# 8266_Download.net
KiCad netlist of a schematic drawn in Altium Designer
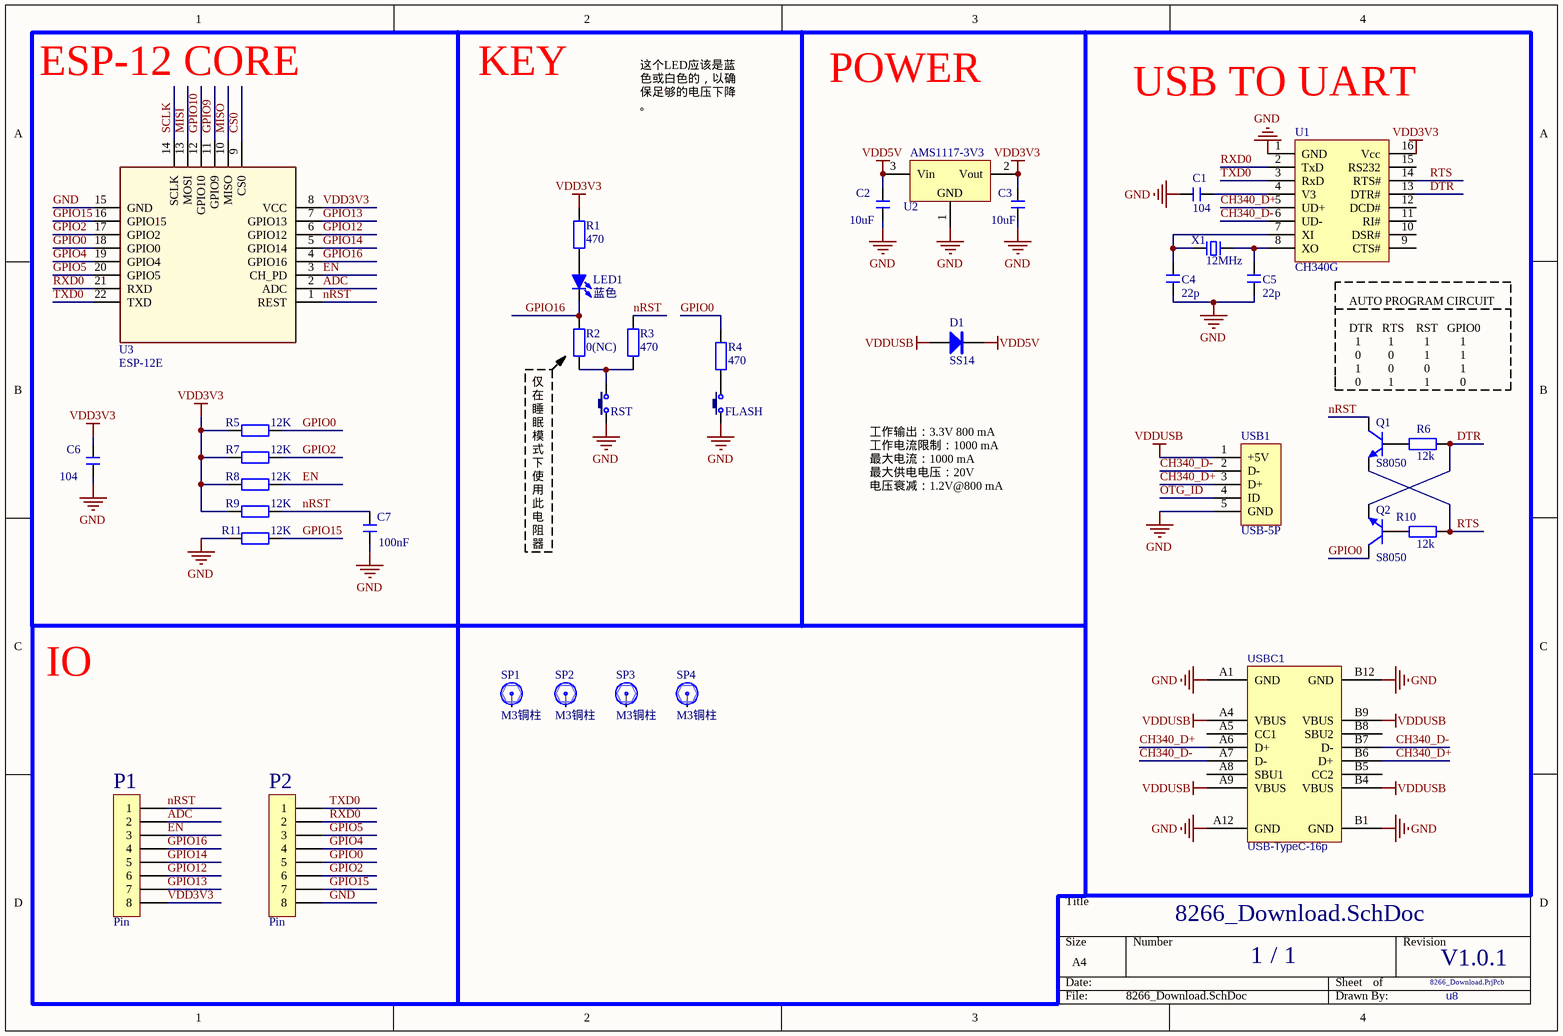
[diagram p0: 8266_Download.SchDoc]

(export (version "E")
  (design (tool "Eeschema 10.0.6"))
  (components
    (comp (ref "C1")
      (value "104")
      (footprint "C 0603_M")
      (description "无极性贴片电容")
      (fields (field (name "版权归属") "源创客"))
      (libsource (lib "U8Library") (part "C"))
    )
    (comp (ref "C2")
      (value "10uF")
      (footprint "C 0603_M")
      (description "无极性贴片电容")
      (fields (field (name "版权归属") "源创客"))
      (libsource (lib "U8Library") (part "C"))
    )
    (comp (ref "C3")
      (value "10uF")
      (footprint "C 0603_M")
      (description "无极性贴片电容")
      (fields (field (name "版权归属") "源创客"))
      (libsource (lib "U8Library") (part "C"))
    )
    (comp (ref "C4")
      (value "22p")
      (footprint "C 0603_M")
      (description "无极性贴片电容")
      (fields (field (name "版权归属") "源创客"))
      (libsource (lib "U8Library") (part "C"))
    )
    (comp (ref "C5")
      (value "22p")
      (footprint "C 0603_M")
      (description "无极性贴片电容")
      (fields (field (name "版权归属") "源创客"))
      (libsource (lib "U8Library") (part "C"))
    )
    (comp (ref "C6")
      (value "104")
      (footprint "C 0603_M")
      (description "无极性贴片电容")
      (fields (field (name "版权归属") "源创客"))
      (libsource (lib "U8Library") (part "C"))
    )
    (comp (ref "C7")
      (value "100nF")
      (footprint "C 0603_M")
      (description "无极性贴片电容")
      (fields (field (name "版权归属") "源创客"))
      (libsource (lib "U8Library") (part "C"))
    )
    (comp (ref "D1")
      (value "SS14")
      (footprint "SMA")
      (description "肖特基二极管")
      (fields (field (name "版权归属") "源创客"))
      (libsource (lib "U8Library") (part "SS14"))
    )
    (comp (ref "FLASH")
      (value "3x6x5")
      (footprint "TSW SMD-3*6*2.5")
      (description "3x6轻触开关")
      (fields (field (name "版权归属") "源创客"))
      (libsource (lib "U8Library") (part "TSW 3x6"))
    )
    (comp (ref "LED1")
      (value "蓝色")
      (footprint "LED 0603B")
      (description "贴片LED")
      (fields (field (name "版权归属") "源创客"))
      (libsource (lib "U8Library") (part "LED-SMD"))
    )
    (comp (ref "P1")
      (value "Pin")
      (footprint "Header_D_8_8x1_2.54")
      (libsource (lib "MZ_接插件库") (part "Header_D_8_8x1_2.54"))
    )
    (comp (ref "P2")
      (value "Pin")
      (footprint "Header_D_8_8x1_2.54")
      (libsource (lib "MZ_接插件库") (part "Header_D_8_8x1_2.54"))
    )
    (comp (ref "Q1")
      (value "S8050")
      (footprint "SOT23-3N")
      (description "高频放大-NPN型")
      (fields (field (name "版权归属") "源创客"))
      (libsource (lib "U8Library") (part "8050-SMD"))
    )
    (comp (ref "Q2")
      (value "S8050")
      (footprint "SOT23-3N")
      (description "高频放大-NPN型")
      (fields (field (name "版权归属") "源创客"))
      (libsource (lib "U8Library") (part "8050-SMD"))
    )
    (comp (ref "R1")
      (value "470")
      (footprint "R 0603_M")
      (description "贴片电阻")
      (fields (field (name "版权归属") "源创客"))
      (libsource (lib "U8Library") (part "R"))
    )
    (comp (ref "R2")
      (value "0(NC)")
      (footprint "R 0603_M")
      (description "贴片电阻")
      (fields (field (name "版权归属") "源创客"))
      (libsource (lib "U8Library") (part "R"))
    )
    (comp (ref "R3")
      (value "470")
      (footprint "R 0603_M")
      (description "贴片电阻")
      (fields (field (name "版权归属") "源创客"))
      (libsource (lib "U8Library") (part "R"))
    )
    (comp (ref "R4")
      (value "470")
      (footprint "R 0603_M")
      (description "贴片电阻")
      (fields (field (name "版权归属") "源创客"))
      (libsource (lib "U8Library") (part "R"))
    )
    (comp (ref "R5")
      (value "12K")
      (footprint "R 0603_M")
      (description "贴片电阻")
      (fields (field (name "版权归属") "源创客"))
      (libsource (lib "U8Library") (part "R"))
    )
    (comp (ref "R6")
      (value "12k")
      (footprint "R 0603_M")
      (description "贴片电阻")
      (fields (field (name "版权归属") "源创客"))
      (libsource (lib "U8Library") (part "R"))
    )
    (comp (ref "R7")
      (value "12K")
      (footprint "R 0603_M")
      (description "贴片电阻")
      (fields (field (name "版权归属") "源创客"))
      (libsource (lib "U8Library") (part "R"))
    )
    (comp (ref "R8")
      (value "12K")
      (footprint "R 0603_M")
      (description "贴片电阻")
      (fields (field (name "版权归属") "源创客"))
      (libsource (lib "U8Library") (part "R"))
    )
    (comp (ref "R9")
      (value "12K")
      (footprint "R 0603_M")
      (description "贴片电阻")
      (fields (field (name "版权归属") "源创客"))
      (libsource (lib "U8Library") (part "R"))
    )
    (comp (ref "R10")
      (value "12k")
      (footprint "R 0603_M")
      (description "贴片电阻")
      (fields (field (name "版权归属") "源创客"))
      (libsource (lib "U8Library") (part "R"))
    )
    (comp (ref "R11")
      (value "12K")
      (footprint "R 0603_M")
      (description "贴片电阻")
      (fields (field (name "版权归属") "源创客"))
      (libsource (lib "U8Library") (part "R"))
    )
    (comp (ref "RST")
      (value "3x6x5")
      (footprint "TSW SMD-3*6*2.5")
      (description "3x6轻触开关")
      (fields (field (name "版权归属") "源创客"))
      (libsource (lib "U8Library") (part "TSW 3x6"))
    )
    (comp (ref "SP1")
      (value "M3铜柱")
      (footprint "M3x4+6_N")
      (description "铜柱")
      (fields (field (name "版权归属") "源创客"))
      (libsource (lib "U8Library") (part "铜柱加头大焊盘"))
    )
    (comp (ref "SP2")
      (value "M3铜柱")
      (footprint "M3x4+6_N")
      (description "铜柱")
      (fields (field (name "版权归属") "源创客"))
      (libsource (lib "U8Library") (part "铜柱加头大焊盘"))
    )
    (comp (ref "SP3")
      (value "M3铜柱")
      (footprint "M3x4+6_N")
      (description "铜柱")
      (fields (field (name "版权归属") "源创客"))
      (libsource (lib "U8Library") (part "铜柱加头大焊盘"))
    )
    (comp (ref "SP4")
      (value "M3铜柱")
      (footprint "M3x4+6_N")
      (description "铜柱")
      (fields (field (name "版权归属") "源创客"))
      (libsource (lib "U8Library") (part "铜柱加头大焊盘"))
    )
    (comp (ref "U1")
      (value "CH340G")
      (footprint "SOP16_L")
      (description "串口转USB")
      (fields (field (name "版权归属") "源创客"))
      (libsource (lib "U8Library") (part "CH340G"))
    )
    (comp (ref "U2")
      (value "AMS1117-3V3")
      (footprint "SOT223_L")
      (description "三端稳压芯片")
      (fields (field (name "版权归属") "源创客"))
      (libsource (lib "U8Library") (part "AMS1117"))
    )
    (comp (ref "U3") (value "ESP-12E") (footprint "esp8266") (libsource (lib "自己的原理图库") (part "ESP-12E")))
    (comp (ref "USB1")
      (value "USB-5P")
      (footprint "USB-MICRO_D")
      (description "微型USB母座")
      (fields (field (name "版权归属") "源创客"))
      (libsource (lib "U8Library") (part "USB-5P"))
    )
    (comp (ref "USBC1")
      (value "USB-TypeC-16p")
      (footprint "TYPE-C-USB-16P-1")
      (libsource (lib "U8Library") (part "USB-TypeC-16p"))
    )
    (comp (ref "X1")
      (value "12MHz")
      (footprint "OSC HC-49S")
      (description "2脚无源脚晶振")
      (fields (field (name "版权归属") "源创客"))
      (libsource (lib "U8Library") (part "XTAL-2P"))
    )
  )
  (nets
    (net (code "1") (name "/ADC") (class "Default")
      (node (ref "P1") (pin "2") (pinfunction "2_2") (pintype "passive"))
      (node (ref "U3") (pin "2") (pinfunction "ADC_2") (pintype "passive"))
    )
    (net (code "2") (name "/CH340_D+") (class "Default")
      (node (ref "U1") (pin "5") (pinfunction "UD+_5") (pintype "passive"))
      (node (ref "USB1") (pin "3") (pinfunction "D+_3") (pintype "passive"))
      (node (ref "USBC1") (pin "A6") (pinfunction "D+_A6") (pintype "passive"))
      (node (ref "USBC1") (pin "B6") (pinfunction "D+_B6") (pintype "passive"))
    )
    (net (code "3") (name "/CH340_D-") (class "Default")
      (node (ref "U1") (pin "6") (pinfunction "UD-_6") (pintype "passive"))
      (node (ref "USB1") (pin "2") (pinfunction "D-_2") (pintype "passive"))
      (node (ref "USBC1") (pin "A7") (pinfunction "D-_A7") (pintype "passive"))
      (node (ref "USBC1") (pin "B7") (pinfunction "D-_B7") (pintype "passive"))
    )
    (net (code "4") (name "/CS0") (class "Default")
      (node (ref "U3") (pin "9") (pinfunction "CS0_9") (pintype "passive"))
    )
    (net (code "5") (name "/DTR") (class "Default")
      (node (ref "Q2") (pin "2") (pinfunction "E_2") (pintype "passive"))
      (node (ref "R6") (pin "1") (pinfunction "1_1") (pintype "passive"))
      (node (ref "U1") (pin "13") (pinfunction "DTR#_13") (pintype "passive"))
    )
    (net (code "6") (name "/EN") (class "Default")
      (node (ref "P1") (pin "3") (pinfunction "3_3") (pintype "passive"))
      (node (ref "R8") (pin "2") (pinfunction "2_2") (pintype "passive"))
      (node (ref "U3") (pin "3") (pinfunction "CH_PD_3") (pintype "passive"))
    )
    (net (code "7") (name "/GPIO0") (class "Default")
      (node (ref "P2") (pin "5") (pinfunction "5_5") (pintype "passive"))
      (node (ref "Q2") (pin "3") (pinfunction "C_3") (pintype "passive"))
      (node (ref "R4") (pin "2") (pinfunction "2_2") (pintype "passive"))
      (node (ref "R5") (pin "2") (pinfunction "2_2") (pintype "passive"))
      (node (ref "U3") (pin "18") (pinfunction "GPIO0_18") (pintype "passive"))
    )
    (net (code "8") (name "/GPIO2") (class "Default")
      (node (ref "P2") (pin "6") (pinfunction "6_6") (pintype "passive"))
      (node (ref "R7") (pin "2") (pinfunction "2_2") (pintype "passive"))
      (node (ref "U3") (pin "17") (pinfunction "GPIO2_17") (pintype "passive"))
    )
    (net (code "9") (name "/GPIO4") (class "Default")
      (node (ref "P2") (pin "4") (pinfunction "4_4") (pintype "passive"))
      (node (ref "U3") (pin "19") (pinfunction "GPIO4_19") (pintype "passive"))
    )
    (net (code "10") (name "/GPIO5") (class "Default")
      (node (ref "P2") (pin "3") (pinfunction "3_3") (pintype "passive"))
      (node (ref "U3") (pin "20") (pinfunction "GPIO5_20") (pintype "passive"))
    )
    (net (code "11") (name "/GPIO9") (class "Default")
      (node (ref "U3") (pin "11") (pinfunction "GPIO9_11") (pintype "passive"))
    )
    (net (code "12") (name "/GPIO10") (class "Default")
      (node (ref "U3") (pin "12") (pinfunction "GPIO10_12") (pintype "passive"))
    )
    (net (code "13") (name "/GPIO12") (class "Default")
      (node (ref "P1") (pin "6") (pinfunction "6_6") (pintype "passive"))
      (node (ref "U3") (pin "6") (pinfunction "GPIO12_6") (pintype "passive"))
    )
    (net (code "14") (name "/GPIO13") (class "Default")
      (node (ref "P1") (pin "7") (pinfunction "7_7") (pintype "passive"))
      (node (ref "U3") (pin "7") (pinfunction "GPIO13_7") (pintype "passive"))
    )
    (net (code "15") (name "/GPIO14") (class "Default")
      (node (ref "P1") (pin "5") (pinfunction "5_5") (pintype "passive"))
      (node (ref "U3") (pin "5") (pinfunction "GPIO14_5") (pintype "passive"))
    )
    (net (code "16") (name "/GPIO15") (class "Default")
      (node (ref "P2") (pin "7") (pinfunction "7_7") (pintype "passive"))
      (node (ref "R11") (pin "2") (pinfunction "2_2") (pintype "passive"))
      (node (ref "U3") (pin "16") (pinfunction "GPIO15_16") (pintype "passive"))
    )
    (net (code "17") (name "/GPIO16") (class "Default")
      (node (ref "LED1") (pin "2") (pinfunction "K_2") (pintype "passive"))
      (node (ref "P1") (pin "4") (pinfunction "4_4") (pintype "passive"))
      (node (ref "R2") (pin "2") (pinfunction "2_2") (pintype "passive"))
      (node (ref "U3") (pin "4") (pinfunction "GPIO16_4") (pintype "passive"))
    )
    (net (code "18") (name "/MISI") (class "Default")
      (node (ref "U3") (pin "13") (pinfunction "MOSI_13") (pintype "passive"))
    )
    (net (code "19") (name "/MISO") (class "Default")
      (node (ref "U3") (pin "10") (pinfunction "MISO_10") (pintype "passive"))
    )
    (net (code "20") (name "/OTG_ID") (class "Default")
      (node (ref "USB1") (pin "4") (pinfunction "ID_4") (pintype "passive"))
    )
    (net (code "21") (name "/RTS") (class "Default")
      (node (ref "Q1") (pin "2") (pinfunction "E_2") (pintype "passive"))
      (node (ref "R10") (pin "1") (pinfunction "1_1") (pintype "passive"))
      (node (ref "U1") (pin "14") (pinfunction "RTS#_14") (pintype "passive"))
    )
    (net (code "22") (name "/RXD0") (class "Default")
      (node (ref "P2") (pin "2") (pinfunction "2_2") (pintype "passive"))
      (node (ref "U1") (pin "2") (pinfunction "TxD_2") (pintype "passive"))
      (node (ref "U3") (pin "21") (pinfunction "RXD_21") (pintype "passive"))
    )
    (net (code "23") (name "/SCLK") (class "Default")
      (node (ref "U3") (pin "14") (pinfunction "SCLK_14") (pintype "passive"))
    )
    (net (code "24") (name "/TXD0") (class "Default")
      (node (ref "P2") (pin "1") (pinfunction "1_1") (pintype "passive"))
      (node (ref "U1") (pin "3") (pinfunction "RxD_3") (pintype "passive"))
      (node (ref "U3") (pin "22") (pinfunction "TXD_22") (pintype "passive"))
    )
    (net (code "25") (name "/nRST") (class "Default")
      (node (ref "C7") (pin "2") (pinfunction "2_2") (pintype "passive"))
      (node (ref "P1") (pin "1") (pinfunction "1_1") (pintype "passive"))
      (node (ref "Q1") (pin "3") (pinfunction "C_3") (pintype "passive"))
      (node (ref "R3") (pin "2") (pinfunction "2_2") (pintype "passive"))
      (node (ref "R9") (pin "2") (pinfunction "2_2") (pintype "passive"))
      (node (ref "U3") (pin "1") (pinfunction "REST_1") (pintype "passive"))
    )
    (net (code "26") (name "GND") (class "Default")
      (node (ref "C1") (pin "2") (pinfunction "2_2") (pintype "passive"))
      (node (ref "C2") (pin "2") (pinfunction "2_2") (pintype "passive"))
      (node (ref "C3") (pin "2") (pinfunction "2_2") (pintype "passive"))
      (node (ref "C4") (pin "2") (pinfunction "2_2") (pintype "passive"))
      (node (ref "C5") (pin "2") (pinfunction "2_2") (pintype "passive"))
      (node (ref "C6") (pin "2") (pinfunction "2_2") (pintype "passive"))
      (node (ref "C7") (pin "1") (pinfunction "1_1") (pintype "passive"))
      (node (ref "FLASH") (pin "1") (pinfunction "1_1") (pintype "passive"))
      (node (ref "P2") (pin "8") (pinfunction "8_8") (pintype "passive"))
      (node (ref "R11") (pin "1") (pinfunction "1_1") (pintype "passive"))
      (node (ref "RST") (pin "1") (pinfunction "1_1") (pintype "passive"))
      (node (ref "U1") (pin "1") (pinfunction "GND_1") (pintype "passive"))
      (node (ref "U2") (pin "1") (pinfunction "GND_1") (pintype "passive"))
      (node (ref "U3") (pin "15") (pinfunction "GND_15") (pintype "passive"))
      (node (ref "USB1") (pin "5") (pinfunction "GND_5") (pintype "passive"))
      (node (ref "USBC1") (pin "A1") (pinfunction "GND_A1") (pintype "passive"))
      (node (ref "USBC1") (pin "A12") (pinfunction "GND_A12") (pintype "passive"))
      (node (ref "USBC1") (pin "B1") (pinfunction "GND_B1") (pintype "passive"))
      (node (ref "USBC1") (pin "B12") (pinfunction "GND_B12") (pintype "passive"))
    )
    (net (code "27") (name "Net-(FLASH-Pad2)") (class "Default")
      (node (ref "FLASH") (pin "2") (pinfunction "2_2") (pintype "passive"))
      (node (ref "R4") (pin "1") (pinfunction "1_1") (pintype "passive"))
    )
    (net (code "28") (name "Net-(LED1-A)") (class "Default")
      (node (ref "LED1") (pin "1") (pinfunction "A_1") (pintype "passive"))
      (node (ref "R1") (pin "1") (pinfunction "1_1") (pintype "passive"))
    )
    (net (code "29") (name "Net-(Q1-B)") (class "Default")
      (node (ref "Q1") (pin "1") (pinfunction "B_1") (pintype "passive"))
      (node (ref "R6") (pin "2") (pinfunction "2_2") (pintype "passive"))
    )
    (net (code "30") (name "Net-(Q2-B)") (class "Default")
      (node (ref "Q2") (pin "1") (pinfunction "B_1") (pintype "passive"))
      (node (ref "R10") (pin "2") (pinfunction "2_2") (pintype "passive"))
    )
    (net (code "31") (name "Net-(R2-Pad1)") (class "Default")
      (node (ref "R2") (pin "1") (pinfunction "1_1") (pintype "passive"))
      (node (ref "R3") (pin "1") (pinfunction "1_1") (pintype "passive"))
      (node (ref "RST") (pin "2") (pinfunction "2_2") (pintype "passive"))
    )
    (net (code "32") (name "Net-(U1-V3)") (class "Default")
      (node (ref "C1") (pin "1") (pinfunction "1_1") (pintype "passive"))
      (node (ref "U1") (pin "4") (pinfunction "V3_4") (pintype "passive"))
    )
    (net (code "33") (name "Net-(U1-XI)") (class "Default")
      (node (ref "C4") (pin "1") (pinfunction "1_1") (pintype "passive"))
      (node (ref "U1") (pin "7") (pinfunction "XI_7") (pintype "passive"))
      (node (ref "X1") (pin "1") (pinfunction "1_1") (pintype "passive"))
    )
    (net (code "34") (name "Net-(U1-XO)") (class "Default")
      (node (ref "C5") (pin "1") (pinfunction "1_1") (pintype "passive"))
      (node (ref "U1") (pin "8") (pinfunction "XO_8") (pintype "passive"))
      (node (ref "X1") (pin "2") (pinfunction "2_2") (pintype "passive"))
    )
    (net (code "35") (name "VDD3V3") (class "Default")
      (node (ref "C3") (pin "1") (pinfunction "1_1") (pintype "passive"))
      (node (ref "C6") (pin "1") (pinfunction "1_1") (pintype "passive"))
      (node (ref "P1") (pin "8") (pinfunction "8_8") (pintype "passive"))
      (node (ref "R1") (pin "2") (pinfunction "2_2") (pintype "passive"))
      (node (ref "R5") (pin "1") (pinfunction "1_1") (pintype "passive"))
      (node (ref "R7") (pin "1") (pinfunction "1_1") (pintype "passive"))
      (node (ref "R8") (pin "1") (pinfunction "1_1") (pintype "passive"))
      (node (ref "R9") (pin "1") (pinfunction "1_1") (pintype "passive"))
      (node (ref "U1") (pin "16") (pinfunction "Vcc_16") (pintype "passive"))
      (node (ref "U2") (pin "2") (pinfunction "Vout_2") (pintype "passive"))
      (node (ref "U3") (pin "8") (pinfunction "VCC_8") (pintype "passive"))
    )
    (net (code "36") (name "VDD5V") (class "Default")
      (node (ref "C2") (pin "1") (pinfunction "1_1") (pintype "passive"))
      (node (ref "D1") (pin "2") (pinfunction "K_2") (pintype "passive"))
      (node (ref "U2") (pin "3") (pinfunction "Vin_3") (pintype "passive"))
    )
    (net (code "37") (name "VDDUSB") (class "Default")
      (node (ref "D1") (pin "1") (pinfunction "A_1") (pintype "passive"))
      (node (ref "USB1") (pin "1") (pinfunction "+5V_1") (pintype "passive"))
      (node (ref "USBC1") (pin "A4") (pinfunction "VBUS_A4") (pintype "passive"))
      (node (ref "USBC1") (pin "A9") (pinfunction "VBUS_A9") (pintype "passive"))
      (node (ref "USBC1") (pin "B4") (pinfunction "VBUS_B4") (pintype "passive"))
      (node (ref "USBC1") (pin "B9") (pinfunction "VBUS_B9") (pintype "passive"))
    )
    (net (code "38") (name "unconnected-(SP1-Pad1)") (class "Default")
      (node (ref "SP1") (pin "1") (pinfunction "1_1") (pintype "passive"))
    )
    (net (code "39") (name "unconnected-(SP2-Pad1)") (class "Default")
      (node (ref "SP2") (pin "1") (pinfunction "1_1") (pintype "passive"))
    )
    (net (code "40") (name "unconnected-(SP3-Pad1)") (class "Default")
      (node (ref "SP3") (pin "1") (pinfunction "1_1") (pintype "passive"))
    )
    (net (code "41") (name "unconnected-(SP4-Pad1)") (class "Default")
      (node (ref "SP4") (pin "1") (pinfunction "1_1") (pintype "passive"))
    )
    (net (code "42") (name "unconnected-(U1-CTS#-Pad9)") (class "Default")
      (node (ref "U1") (pin "9") (pinfunction "CTS#_9") (pintype "passive"))
    )
    (net (code "43") (name "unconnected-(U1-DCD#-Pad12)") (class "Default")
      (node (ref "U1") (pin "12") (pinfunction "DCD#_12") (pintype "passive"))
    )
    (net (code "44") (name "unconnected-(U1-DSR#-Pad10)") (class "Default")
      (node (ref "U1") (pin "10") (pinfunction "DSR#_10") (pintype "passive"))
    )
    (net (code "45") (name "unconnected-(U1-RI#-Pad11)") (class "Default")
      (node (ref "U1") (pin "11") (pinfunction "RI#_11") (pintype "passive"))
    )
    (net (code "46") (name "unconnected-(U1-RS232-Pad15)") (class "Default")
      (node (ref "U1") (pin "15") (pinfunction "RS232_15") (pintype "passive"))
    )
    (net (code "47") (name "unconnected-(USBC1-CC1-PadA5)") (class "Default")
      (node (ref "USBC1") (pin "A5") (pinfunction "CC1_A5") (pintype "passive"))
    )
    (net (code "48") (name "unconnected-(USBC1-CC2-PadB5)") (class "Default")
      (node (ref "USBC1") (pin "B5") (pinfunction "CC2_B5") (pintype "passive"))
    )
    (net (code "49") (name "unconnected-(USBC1-SBU1-PadA8)") (class "Default")
      (node (ref "USBC1") (pin "A8") (pinfunction "SBU1_A8") (pintype "passive"))
    )
    (net (code "50") (name "unconnected-(USBC1-SBU2-PadB8)") (class "Default")
      (node (ref "USBC1") (pin "B8") (pinfunction "SBU2_B8") (pintype "passive"))
    )
  )
)
